# Street_Fighter_v1_3.net
KiCad netlist of a schematic drawn in EAGLE
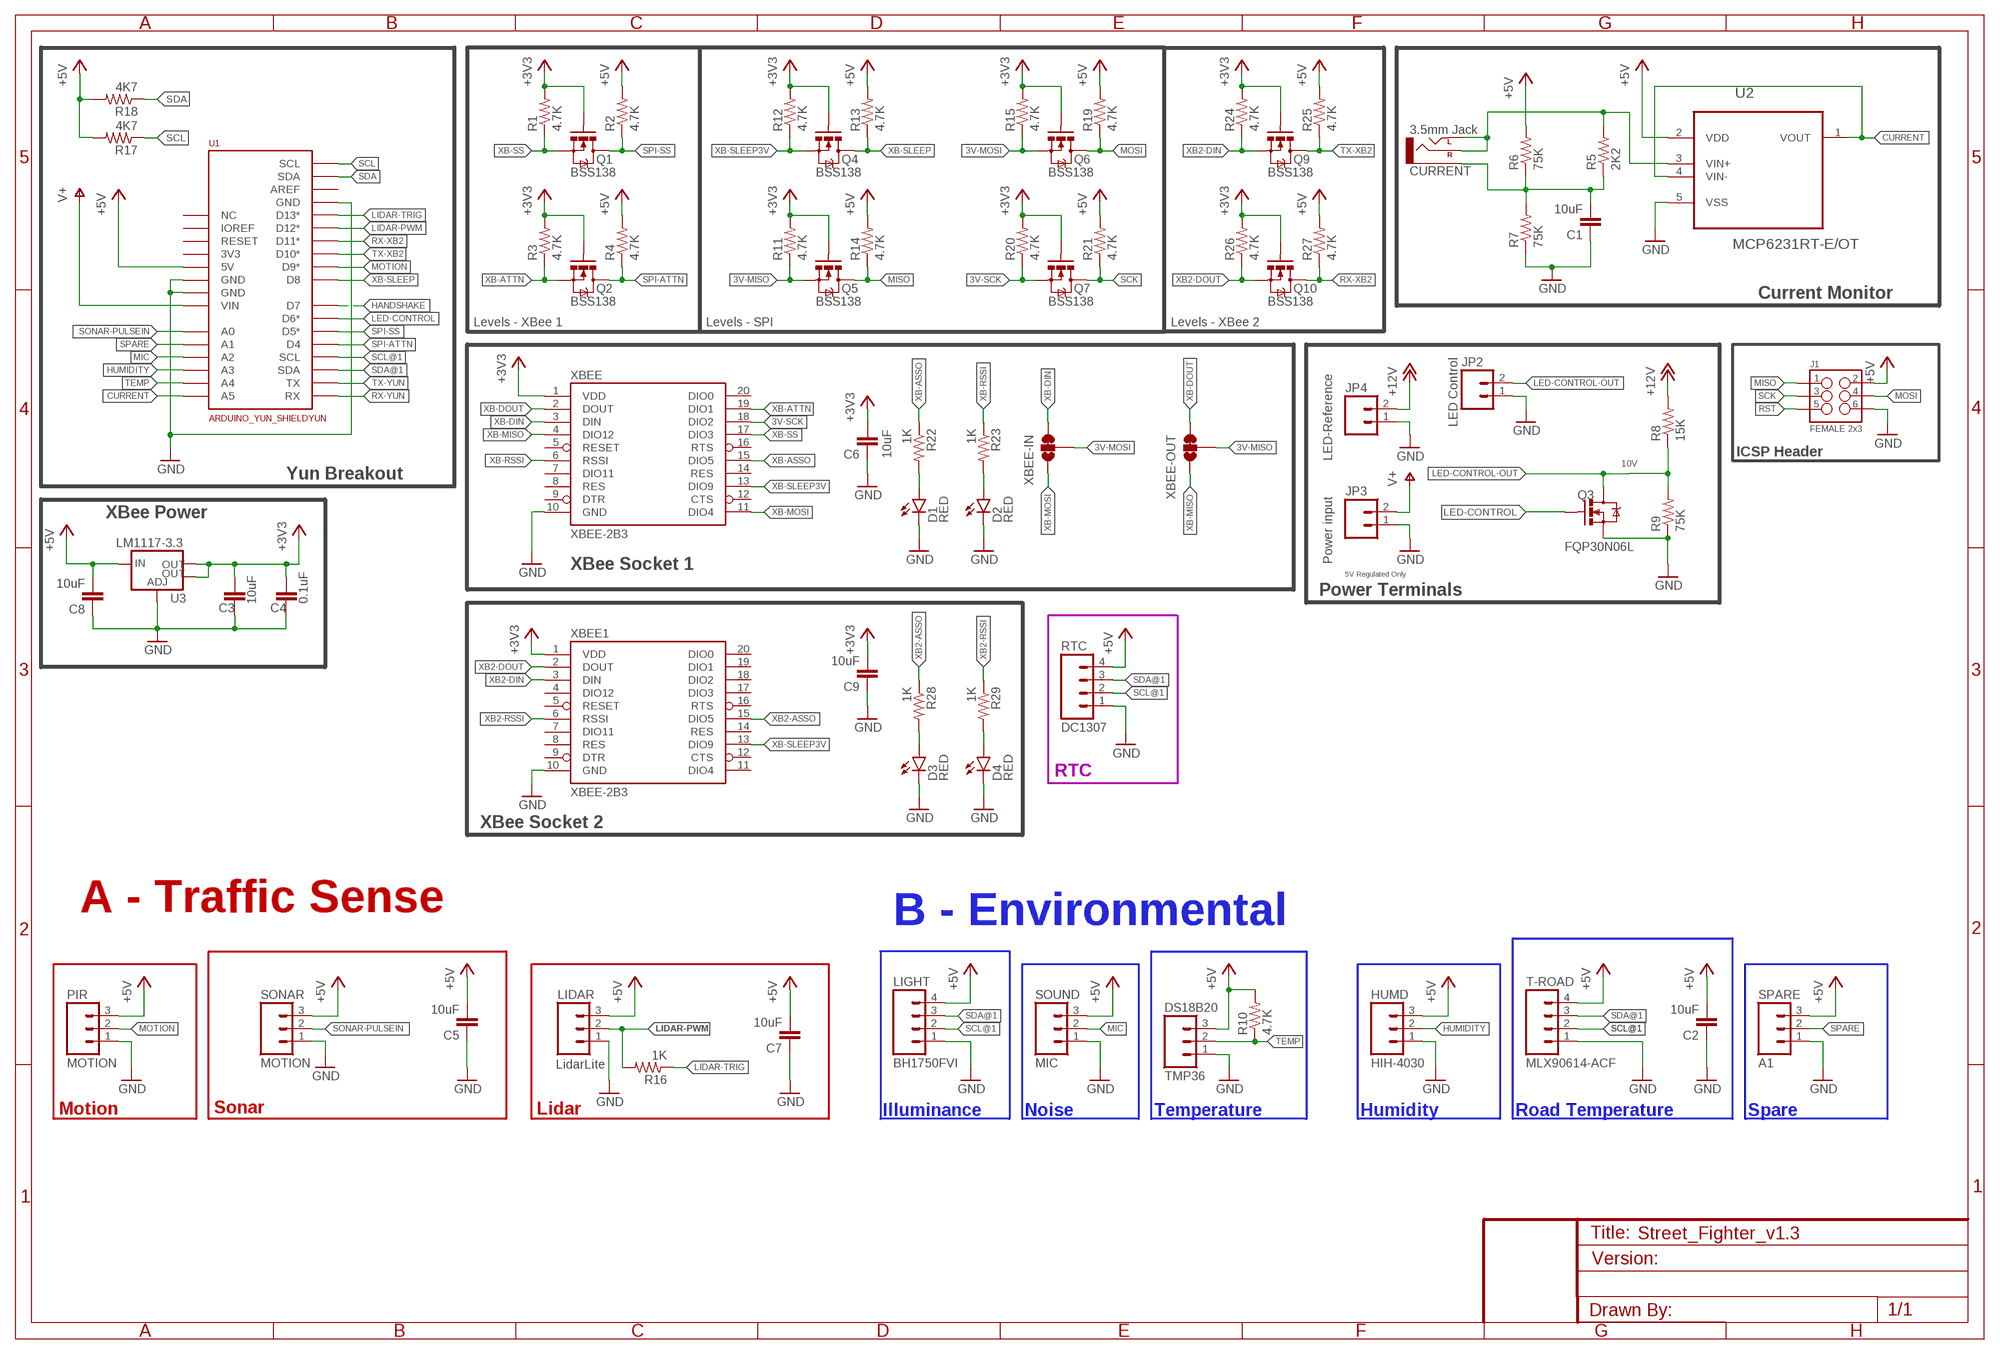
[diagram p0: schematic, sheet 1]

(export (version "E")
  (design (tool "Eeschema 10.0.6"))
  (components
    (comp (ref "C1")
      (value "10uF")
      (footprint "eagle-import:1206")
      (libsource (lib "eagle-import") (part "10UF-6.3V-20%(1206)"))
    )
    (comp (ref "C2")
      (value "10uF")
      (footprint "eagle-import:1206")
      (libsource (lib "eagle-import") (part "10UF-6.3V-20%(1206)"))
    )
    (comp (ref "C3")
      (value "10uF")
      (footprint "eagle-import:1206")
      (libsource (lib "eagle-import") (part "10UF-6.3V-20%(1206)"))
    )
    (comp (ref "C4")
      (value "0.1uF")
      (footprint "eagle-import:1206")
      (libsource (lib "eagle-import") (part "10UF-6.3V-20%(1206)"))
    )
    (comp (ref "C5")
      (value "10uF")
      (footprint "eagle-import:1206")
      (libsource (lib "eagle-import") (part "10UF-6.3V-20%(1206)"))
    )
    (comp (ref "C6")
      (value "10uF")
      (footprint "eagle-import:1206")
      (libsource (lib "eagle-import") (part "10UF-6.3V-20%(1206)"))
    )
    (comp (ref "C7")
      (value "10uF")
      (footprint "eagle-import:1206")
      (libsource (lib "eagle-import") (part "10UF-6.3V-20%(1206)"))
    )
    (comp (ref "C8")
      (value "10uF")
      (footprint "eagle-import:1206")
      (libsource (lib "eagle-import") (part "10UF-6.3V-20%(1206)"))
    )
    (comp (ref "C9")
      (value "10uF")
      (footprint "eagle-import:1206")
      (libsource (lib "eagle-import") (part "10UF-6.3V-20%(1206)"))
    )
    (comp (ref "CURRENT")
      (value "3.5mm Jack")
      (footprint "eagle-import:AUDIO-JACK")
      (libsource (lib "eagle-import") (part "AUDIO-JACKPTH"))
    )
    (comp (ref "D1")
      (value "RED")
      (footprint "eagle-import:LED-1206")
      (libsource (lib "eagle-import") (part "LED-RED1206"))
    )
    (comp (ref "D2")
      (value "RED")
      (footprint "eagle-import:LED-1206")
      (libsource (lib "eagle-import") (part "LED-RED1206"))
    )
    (comp (ref "D3")
      (value "RED")
      (footprint "eagle-import:LED-1206")
      (libsource (lib "eagle-import") (part "LED-RED1206"))
    )
    (comp (ref "D4")
      (value "RED")
      (footprint "eagle-import:LED-1206")
      (libsource (lib "eagle-import") (part "LED-RED1206"))
    )
    (comp (ref "DS18B20")
      (value "TMP36")
      (footprint "eagle-import:1X03")
      (libsource (lib "eagle-import") (part "M03PTH"))
    )
    (comp (ref "HUMD")
      (value "HIH-4030")
      (footprint "eagle-import:1X03")
      (libsource (lib "eagle-import") (part "M03PTH"))
    )
    (comp (ref "J1")
      (value "FEMALE 2x3")
      (footprint "eagle-import:2X3")
      (libsource (lib "eagle-import") (part "M03X2FEMALE"))
    )
    (comp (ref "JP2")
      (value "LED Control")
      (footprint "eagle-import:1X02_LONGPADS")
      (libsource (lib "eagle-import") (part "M02PTH3"))
    )
    (comp (ref "JP3")
      (value "Power input")
      (footprint "eagle-import:1X02_LONGPADS")
      (libsource (lib "eagle-import") (part "M02PTH3"))
    )
    (comp (ref "JP4")
      (value "LED-Reference")
      (footprint "eagle-import:1X02_LONGPADS")
      (libsource (lib "eagle-import") (part "M02PTH3"))
    )
    (comp (ref "LIDAR")
      (value "LidarLite")
      (footprint "eagle-import:1X03")
      (libsource (lib "eagle-import") (part "M03PTH"))
    )
    (comp (ref "LIGHT")
      (value "BH1750FVI")
      (footprint "eagle-import:1X04")
      (libsource (lib "eagle-import") (part "M04PTH"))
    )
    (comp (ref "PIR")
      (value "MOTION")
      (footprint "eagle-import:1X03")
      (libsource (lib "eagle-import") (part "M03PTH"))
    )
    (comp (ref "Q1")
      (value "BSS138")
      (footprint "eagle-import:SOT23")
      (libsource (lib "eagle-import") (part "MOSFET-NCHANNELBSS123LT1G"))
    )
    (comp (ref "Q2")
      (value "BSS138")
      (footprint "eagle-import:SOT23")
      (libsource (lib "eagle-import") (part "MOSFET-NCHANNELBSS123LT1G"))
    )
    (comp (ref "Q3")
      (value "FQP30N06L")
      (footprint "eagle-import:TO220V")
      (libsource (lib "eagle-import") (part "MOSFET-NCHANNELFQP30N06L"))
    )
    (comp (ref "Q4")
      (value "BSS138")
      (footprint "eagle-import:SOT23")
      (libsource (lib "eagle-import") (part "MOSFET-NCHANNELBSS123LT1G"))
    )
    (comp (ref "Q5")
      (value "BSS138")
      (footprint "eagle-import:SOT23")
      (libsource (lib "eagle-import") (part "MOSFET-NCHANNELBSS123LT1G"))
    )
    (comp (ref "Q6")
      (value "BSS138")
      (footprint "eagle-import:SOT23")
      (libsource (lib "eagle-import") (part "MOSFET-NCHANNELBSS123LT1G"))
    )
    (comp (ref "Q7")
      (value "BSS138")
      (footprint "eagle-import:SOT23")
      (libsource (lib "eagle-import") (part "MOSFET-NCHANNELBSS123LT1G"))
    )
    (comp (ref "Q9")
      (value "BSS138")
      (footprint "eagle-import:SOT23")
      (libsource (lib "eagle-import") (part "MOSFET-NCHANNELBSS123LT1G"))
    )
    (comp (ref "Q10")
      (value "BSS138")
      (footprint "eagle-import:SOT23")
      (libsource (lib "eagle-import") (part "MOSFET-NCHANNELBSS123LT1G"))
    )
    (comp (ref "R1")
      (value "4.7K")
      (footprint "eagle-import:1206")
      (libsource (lib "eagle-import") (part "RESISTOR1206"))
    )
    (comp (ref "R2")
      (value "4.7K")
      (footprint "eagle-import:1206")
      (libsource (lib "eagle-import") (part "RESISTOR1206"))
    )
    (comp (ref "R3")
      (value "4.7K")
      (footprint "eagle-import:1206")
      (libsource (lib "eagle-import") (part "RESISTOR1206"))
    )
    (comp (ref "R4")
      (value "4.7K")
      (footprint "eagle-import:1206")
      (libsource (lib "eagle-import") (part "RESISTOR1206"))
    )
    (comp (ref "R5")
      (value "2K2")
      (footprint "eagle-import:1206")
      (libsource (lib "eagle-import") (part "RESISTOR1206"))
    )
    (comp (ref "R6")
      (value "75K")
      (footprint "eagle-import:1206")
      (libsource (lib "eagle-import") (part "RESISTOR1206"))
    )
    (comp (ref "R7")
      (value "75K")
      (footprint "eagle-import:1206")
      (libsource (lib "eagle-import") (part "RESISTOR1206"))
    )
    (comp (ref "R8")
      (value "15K")
      (footprint "eagle-import:1206")
      (libsource (lib "eagle-import") (part "RESISTOR1206"))
    )
    (comp (ref "R9")
      (value "75K")
      (footprint "eagle-import:1206")
      (libsource (lib "eagle-import") (part "RESISTOR1206"))
    )
    (comp (ref "R10")
      (value "4.7K")
      (footprint "eagle-import:1206")
      (libsource (lib "eagle-import") (part "RESISTOR1206"))
    )
    (comp (ref "R11")
      (value "4.7K")
      (footprint "eagle-import:1206")
      (libsource (lib "eagle-import") (part "RESISTOR1206"))
    )
    (comp (ref "R12")
      (value "4.7K")
      (footprint "eagle-import:1206")
      (libsource (lib "eagle-import") (part "RESISTOR1206"))
    )
    (comp (ref "R13")
      (value "4.7K")
      (footprint "eagle-import:1206")
      (libsource (lib "eagle-import") (part "RESISTOR1206"))
    )
    (comp (ref "R14")
      (value "4.7K")
      (footprint "eagle-import:1206")
      (libsource (lib "eagle-import") (part "RESISTOR1206"))
    )
    (comp (ref "R15")
      (value "4.7K")
      (footprint "eagle-import:1206")
      (libsource (lib "eagle-import") (part "RESISTOR1206"))
    )
    (comp (ref "R16")
      (value "1K")
      (footprint "eagle-import:1206")
      (libsource (lib "eagle-import") (part "RESISTOR1206"))
    )
    (comp (ref "R17")
      (value "4K7")
      (footprint "eagle-import:1206")
      (libsource (lib "eagle-import") (part "RESISTOR1206"))
    )
    (comp (ref "R18")
      (value "4K7")
      (footprint "eagle-import:1206")
      (libsource (lib "eagle-import") (part "RESISTOR1206"))
    )
    (comp (ref "R19")
      (value "4.7K")
      (footprint "eagle-import:1206")
      (libsource (lib "eagle-import") (part "RESISTOR1206"))
    )
    (comp (ref "R20")
      (value "4.7K")
      (footprint "eagle-import:1206")
      (libsource (lib "eagle-import") (part "RESISTOR1206"))
    )
    (comp (ref "R21")
      (value "4.7K")
      (footprint "eagle-import:1206")
      (libsource (lib "eagle-import") (part "RESISTOR1206"))
    )
    (comp (ref "R22")
      (value "1K")
      (footprint "eagle-import:1206")
      (libsource (lib "eagle-import") (part "RESISTOR1206"))
    )
    (comp (ref "R23")
      (value "1K")
      (footprint "eagle-import:1206")
      (libsource (lib "eagle-import") (part "RESISTOR1206"))
    )
    (comp (ref "R24")
      (value "4.7K")
      (footprint "eagle-import:1206")
      (libsource (lib "eagle-import") (part "RESISTOR1206"))
    )
    (comp (ref "R25")
      (value "4.7K")
      (footprint "eagle-import:1206")
      (libsource (lib "eagle-import") (part "RESISTOR1206"))
    )
    (comp (ref "R26")
      (value "4.7K")
      (footprint "eagle-import:1206")
      (libsource (lib "eagle-import") (part "RESISTOR1206"))
    )
    (comp (ref "R27")
      (value "4.7K")
      (footprint "eagle-import:1206")
      (libsource (lib "eagle-import") (part "RESISTOR1206"))
    )
    (comp (ref "R28")
      (value "1K")
      (footprint "eagle-import:1206")
      (libsource (lib "eagle-import") (part "RESISTOR1206"))
    )
    (comp (ref "R29")
      (value "1K")
      (footprint "eagle-import:1206")
      (libsource (lib "eagle-import") (part "RESISTOR1206"))
    )
    (comp (ref "RTC")
      (value "DC1307")
      (footprint "eagle-import:1X04")
      (libsource (lib "eagle-import") (part "M04PTH"))
    )
    (comp (ref "SONAR")
      (value "MOTION")
      (footprint "eagle-import:1X03")
      (libsource (lib "eagle-import") (part "M03PTH"))
    )
    (comp (ref "SOUND")
      (value "MIC")
      (footprint "eagle-import:1X03")
      (libsource (lib "eagle-import") (part "M03PTH"))
    )
    (comp (ref "SPARE")
      (value "A1")
      (footprint "eagle-import:1X03")
      (libsource (lib "eagle-import") (part "M03PTH"))
    )
    (comp (ref "T-ROAD")
      (value "MLX90614-ACF")
      (footprint "eagle-import:1X04")
      (libsource (lib "eagle-import") (part "M04PTH"))
    )
    (comp (ref "U1")
      (value "ARDUINO_YUN_SHIELDYUN")
      (footprint "eagle-import:DUEMILANOVE_VIAS")
      (libsource (lib "eagle-import") (part "ARDUINO_YUN_SHIELDYUN"))
    )
    (comp (ref "U2")
      (value "MCP6231RT-E/OT")
      (footprint "eagle-import:SOT95P270X145-5N")
      (libsource (lib "eagle-import") (part "MCP6231RT-E/OT"))
    )
    (comp (ref "U3")
      (value "LM1117-3.3")
      (footprint "eagle-import:SOT223")
      (libsource (lib "eagle-import") (part "V_REG_LM1117SOT223"))
    )
    (comp (ref "XBEE")
      (value "XBEE-2B3")
      (footprint "eagle-import:XBEE-SMD")
      (libsource (lib "eagle-import") (part "XBEE-2B3"))
    )
    (comp (ref "XBEE-IN")
      (value "JUMPER-PAD-3-2OF3_NC_BY_TRACE_SMALL")
      (footprint "eagle-import:PAD-JUMPER-3-2OF3_NC_BY_TRACE_YES_SILK_FULL_BOX")
      (libsource (lib "eagle-import") (part "JUMPER-PAD-3-2OF3_NC_BY_TRACE_SMALL"))
    )
    (comp (ref "XBEE-OUT")
      (value "JUMPER-PAD-3-2OF3_NC_BY_TRACE_SMALL")
      (footprint "eagle-import:PAD-JUMPER-3-2OF3_NC_BY_TRACE_YES_SILK_FULL_BOX")
      (libsource (lib "eagle-import") (part "JUMPER-PAD-3-2OF3_NC_BY_TRACE_SMALL"))
    )
    (comp (ref "XBEE1")
      (value "XBEE-2B3")
      (footprint "eagle-import:XBEE-SMD")
      (libsource (lib "eagle-import") (part "XBEE-2B3"))
    )
  )
  (nets
    (net (code "1") (name "+3V3") (class "Default")
      (node (ref "C3") (pin "2") (pinfunction "2_2") (pintype "passive"))
      (node (ref "C4") (pin "2") (pinfunction "2_2") (pintype "passive"))
      (node (ref "C6") (pin "2") (pinfunction "2_2") (pintype "passive"))
      (node (ref "C9") (pin "2") (pinfunction "2_2") (pintype "passive"))
      (node (ref "Q1") (pin "1") (pinfunction "G_1") (pintype "passive"))
      (node (ref "Q10") (pin "1") (pinfunction "G_1") (pintype "passive"))
      (node (ref "Q2") (pin "1") (pinfunction "G_1") (pintype "passive"))
      (node (ref "Q4") (pin "1") (pinfunction "G_1") (pintype "passive"))
      (node (ref "Q5") (pin "1") (pinfunction "G_1") (pintype "passive"))
      (node (ref "Q6") (pin "1") (pinfunction "G_1") (pintype "passive"))
      (node (ref "Q7") (pin "1") (pinfunction "G_1") (pintype "passive"))
      (node (ref "Q9") (pin "1") (pinfunction "G_1") (pintype "passive"))
      (node (ref "R1") (pin "2") (pinfunction "2_2") (pintype "passive"))
      (node (ref "R11") (pin "2") (pinfunction "2_2") (pintype "passive"))
      (node (ref "R12") (pin "2") (pinfunction "2_2") (pintype "passive"))
      (node (ref "R15") (pin "2") (pinfunction "2_2") (pintype "passive"))
      (node (ref "R20") (pin "2") (pinfunction "2_2") (pintype "passive"))
      (node (ref "R24") (pin "2") (pinfunction "2_2") (pintype "passive"))
      (node (ref "R26") (pin "2") (pinfunction "2_2") (pintype "passive"))
      (node (ref "R3") (pin "2") (pinfunction "2_2") (pintype "passive"))
      (node (ref "U3") (pin "2") (pinfunction "OUT_2") (pintype "output"))
      (node (ref "U3") (pin "4") (pinfunction "OUT_4") (pintype "output"))
      (node (ref "XBEE") (pin "1") (pinfunction "VDD_1") (pintype "power_in"))
      (node (ref "XBEE1") (pin "1") (pinfunction "VDD_1") (pintype "power_in"))
    )
    (net (code "2") (name "+5V") (class "Default")
      (node (ref "C2") (pin "2") (pinfunction "2_2") (pintype "passive"))
      (node (ref "C5") (pin "2") (pinfunction "2_2") (pintype "passive"))
      (node (ref "C7") (pin "2") (pinfunction "2_2") (pintype "passive"))
      (node (ref "C8") (pin "2") (pinfunction "2_2") (pintype "passive"))
      (node (ref "DS18B20") (pin "3") (pinfunction "3_3") (pintype "passive"))
      (node (ref "HUMD") (pin "3") (pinfunction "3_3") (pintype "passive"))
      (node (ref "J1") (pin "2") (pinfunction "2_2") (pintype "bidirectional"))
      (node (ref "LIDAR") (pin "3") (pinfunction "3_3") (pintype "passive"))
      (node (ref "LIGHT") (pin "4") (pinfunction "4_4") (pintype "passive"))
      (node (ref "PIR") (pin "3") (pinfunction "3_3") (pintype "passive"))
      (node (ref "R10") (pin "2") (pinfunction "2_2") (pintype "passive"))
      (node (ref "R13") (pin "2") (pinfunction "2_2") (pintype "passive"))
      (node (ref "R14") (pin "2") (pinfunction "2_2") (pintype "passive"))
      (node (ref "R17") (pin "2") (pinfunction "2_2") (pintype "passive"))
      (node (ref "R18") (pin "2") (pinfunction "2_2") (pintype "passive"))
      (node (ref "R19") (pin "2") (pinfunction "2_2") (pintype "passive"))
      (node (ref "R2") (pin "2") (pinfunction "2_2") (pintype "passive"))
      (node (ref "R21") (pin "2") (pinfunction "2_2") (pintype "passive"))
      (node (ref "R25") (pin "2") (pinfunction "2_2") (pintype "passive"))
      (node (ref "R27") (pin "2") (pinfunction "2_2") (pintype "passive"))
      (node (ref "R4") (pin "2") (pinfunction "2_2") (pintype "passive"))
      (node (ref "R6") (pin "2") (pinfunction "2_2") (pintype "passive"))
      (node (ref "RTC") (pin "4") (pinfunction "4_4") (pintype "passive"))
      (node (ref "SONAR") (pin "3") (pinfunction "3_3") (pintype "passive"))
      (node (ref "SOUND") (pin "3") (pinfunction "3_3") (pintype "passive"))
      (node (ref "SPARE") (pin "3") (pinfunction "3_3") (pintype "passive"))
      (node (ref "T-ROAD") (pin "4") (pinfunction "4_4") (pintype "passive"))
      (node (ref "U1") (pin "5V") (pinfunction "5V_5V") (pintype "power_in"))
      (node (ref "U2") (pin "2") (pinfunction "VDD_2") (pintype "power_in"))
      (node (ref "U3") (pin "3") (pinfunction "IN_3") (pintype "input"))
    )
    (net (code "3") (name "+12V") (class "Default")
      (node (ref "JP4") (pin "2") (pinfunction "2_2") (pintype "passive"))
      (node (ref "R8") (pin "2") (pinfunction "2_2") (pintype "passive"))
    )
    (net (code "4") (name "/3V3") (class "Default")
      (node (ref "U1") (pin "3V3") (pinfunction "3V3_3V3") (pintype "power_in"))
    )
    (net (code "5") (name "3V-MISO") (class "Default")
      (node (ref "Q5") (pin "2") (pinfunction "S_2") (pintype "passive"))
      (node (ref "R11") (pin "1") (pinfunction "1_1") (pintype "passive"))
      (node (ref "XBEE-OUT") (pin "2") (pinfunction "2_2") (pintype "passive"))
    )
    (net (code "6") (name "3V-MOSI") (class "Default")
      (node (ref "Q6") (pin "2") (pinfunction "S_2") (pintype "passive"))
      (node (ref "R15") (pin "1") (pinfunction "1_1") (pintype "passive"))
      (node (ref "XBEE-IN") (pin "2") (pinfunction "2_2") (pintype "passive"))
    )
    (net (code "7") (name "3V-SCK") (class "Default")
      (node (ref "Q7") (pin "2") (pinfunction "S_2") (pintype "passive"))
      (node (ref "R20") (pin "1") (pinfunction "1_1") (pintype "passive"))
      (node (ref "XBEE") (pin "18") (pinfunction "DIO2_18") (pintype "bidirectional"))
    )
    (net (code "8") (name "CURRENT") (class "Default")
      (node (ref "U1") (pin "A5") (pinfunction "A5_A5") (pintype "bidirectional"))
      (node (ref "U2") (pin "1") (pinfunction "VOUT_1") (pintype "output"))
      (node (ref "U2") (pin "4") (pinfunction "VIN-_4") (pintype "input"))
    )
    (net (code "9") (name "GND") (class "Default")
      (node (ref "C1") (pin "1") (pinfunction "1_1") (pintype "passive"))
      (node (ref "C2") (pin "1") (pinfunction "1_1") (pintype "passive"))
      (node (ref "C3") (pin "1") (pinfunction "1_1") (pintype "passive"))
      (node (ref "C4") (pin "1") (pinfunction "1_1") (pintype "passive"))
      (node (ref "C5") (pin "1") (pinfunction "1_1") (pintype "passive"))
      (node (ref "C6") (pin "1") (pinfunction "1_1") (pintype "passive"))
      (node (ref "C7") (pin "1") (pinfunction "1_1") (pintype "passive"))
      (node (ref "C8") (pin "1") (pinfunction "1_1") (pintype "passive"))
      (node (ref "C9") (pin "1") (pinfunction "1_1") (pintype "passive"))
      (node (ref "D1") (pin "C") (pinfunction "C_C") (pintype "passive"))
      (node (ref "D2") (pin "C") (pinfunction "C_C") (pintype "passive"))
      (node (ref "D3") (pin "C") (pinfunction "C_C") (pintype "passive"))
      (node (ref "D4") (pin "C") (pinfunction "C_C") (pintype "passive"))
      (node (ref "DS18B20") (pin "1") (pinfunction "1_1") (pintype "passive"))
      (node (ref "HUMD") (pin "1") (pinfunction "1_1") (pintype "passive"))
      (node (ref "J1") (pin "6") (pinfunction "6_6") (pintype "bidirectional"))
      (node (ref "JP2") (pin "1") (pinfunction "1_1") (pintype "passive"))
      (node (ref "JP3") (pin "1") (pinfunction "1_1") (pintype "passive"))
      (node (ref "JP4") (pin "1") (pinfunction "1_1") (pintype "passive"))
      (node (ref "LIDAR") (pin "1") (pinfunction "1_1") (pintype "passive"))
      (node (ref "LIGHT") (pin "1") (pinfunction "1_1") (pintype "passive"))
      (node (ref "PIR") (pin "1") (pinfunction "1_1") (pintype "passive"))
      (node (ref "Q3") (pin "3") (pinfunction "S_3") (pintype "passive"))
      (node (ref "R7") (pin "1") (pinfunction "1_1") (pintype "passive"))
      (node (ref "R9") (pin "1") (pinfunction "1_1") (pintype "passive"))
      (node (ref "RTC") (pin "1") (pinfunction "1_1") (pintype "passive"))
      (node (ref "SONAR") (pin "1") (pinfunction "1_1") (pintype "passive"))
      (node (ref "SOUND") (pin "1") (pinfunction "1_1") (pintype "passive"))
      (node (ref "SPARE") (pin "1") (pinfunction "1_1") (pintype "passive"))
      (node (ref "T-ROAD") (pin "1") (pinfunction "1_1") (pintype "passive"))
      (node (ref "U1") (pin "GND") (pinfunction "GND_GND") (pintype "power_in"))
      (node (ref "U1") (pin "GND@0") (pinfunction "GND_GND@0") (pintype "power_in"))
      (node (ref "U1") (pin "GND@1") (pinfunction "GND_GND@1") (pintype "power_in"))
      (node (ref "U2") (pin "5") (pinfunction "VSS_5") (pintype "passive"))
      (node (ref "U3") (pin "1") (pinfunction "ADJ_1") (pintype "input"))
      (node (ref "XBEE") (pin "10") (pinfunction "GND_10") (pintype "power_in"))
      (node (ref "XBEE1") (pin "10") (pinfunction "GND_10") (pintype "power_in"))
    )
    (net (code "10") (name "HANDSHAKE") (class "Default")
      (node (ref "U1") (pin "7") (pinfunction "D7_7") (pintype "bidirectional"))
    )
    (net (code "11") (name "HUMIDITY") (class "Default")
      (node (ref "HUMD") (pin "2") (pinfunction "2_2") (pintype "passive"))
      (node (ref "U1") (pin "A3") (pinfunction "A3_A3") (pintype "bidirectional"))
    )
    (net (code "12") (name "LED-CONTROL") (class "Default")
      (node (ref "Q3") (pin "1") (pinfunction "G_1") (pintype "passive"))
      (node (ref "U1") (pin "6") (pinfunction "D6*_6") (pintype "bidirectional"))
    )
    (net (code "13") (name "LED-CONTROL-OUT") (class "Default")
      (node (ref "JP2") (pin "2") (pinfunction "2_2") (pintype "passive"))
      (node (ref "Q3") (pin "2") (pinfunction "D_2") (pintype "passive"))
      (node (ref "R8") (pin "1") (pinfunction "1_1") (pintype "passive"))
      (node (ref "R9") (pin "2") (pinfunction "2_2") (pintype "passive"))
    )
    (net (code "14") (name "LIDAR-PWM") (class "Default")
      (node (ref "LIDAR") (pin "2") (pinfunction "2_2") (pintype "passive"))
      (node (ref "R16") (pin "2") (pinfunction "2_2") (pintype "passive"))
      (node (ref "U1") (pin "12") (pinfunction "D12*_12") (pintype "bidirectional"))
    )
    (net (code "15") (name "LIDAR-TRIG") (class "Default")
      (node (ref "R16") (pin "1") (pinfunction "1_1") (pintype "passive"))
      (node (ref "U1") (pin "13") (pinfunction "D13*_13") (pintype "bidirectional"))
    )
    (net (code "16") (name "MIC") (class "Default")
      (node (ref "SOUND") (pin "2") (pinfunction "2_2") (pintype "passive"))
      (node (ref "U1") (pin "A2") (pinfunction "A2_A2") (pintype "bidirectional"))
    )
    (net (code "17") (name "MISO") (class "Default")
      (node (ref "J1") (pin "1") (pinfunction "1_1") (pintype "bidirectional"))
      (node (ref "Q5") (pin "3") (pinfunction "D_3") (pintype "passive"))
      (node (ref "R14") (pin "1") (pinfunction "1_1") (pintype "passive"))
    )
    (net (code "18") (name "MOSI") (class "Default")
      (node (ref "J1") (pin "4") (pinfunction "4_4") (pintype "bidirectional"))
      (node (ref "Q6") (pin "3") (pinfunction "D_3") (pintype "passive"))
      (node (ref "R19") (pin "1") (pinfunction "1_1") (pintype "passive"))
    )
    (net (code "19") (name "MOTION") (class "Default")
      (node (ref "PIR") (pin "2") (pinfunction "2_2") (pintype "passive"))
      (node (ref "U1") (pin "9") (pinfunction "D9*_9") (pintype "bidirectional"))
    )
    (net (code "20") (name "Net-(C1-Pad2)") (class "Default")
      (node (ref "C1") (pin "2") (pinfunction "2_2") (pintype "passive"))
      (node (ref "CURRENT") (pin "SLEEVE") (pinfunction "SLEEVE_SLEEVE") (pintype "bidirectional"))
      (node (ref "R5") (pin "1") (pinfunction "1_1") (pintype "passive"))
      (node (ref "R6") (pin "1") (pinfunction "1_1") (pintype "passive"))
      (node (ref "R7") (pin "2") (pinfunction "2_2") (pintype "passive"))
    )
    (net (code "21") (name "Net-(CURRENT-LEFT)") (class "Default")
      (node (ref "CURRENT") (pin "RING") (pinfunction "RIGHT_RING") (pintype "bidirectional"))
      (node (ref "CURRENT") (pin "TIP") (pinfunction "LEFT_TIP") (pintype "bidirectional"))
      (node (ref "R5") (pin "2") (pinfunction "2_2") (pintype "passive"))
      (node (ref "U2") (pin "3") (pinfunction "VIN+_3") (pintype "input"))
    )
    (net (code "22") (name "Net-(D1-PadA)") (class "Default")
      (node (ref "D1") (pin "A") (pinfunction "A_A") (pintype "passive"))
      (node (ref "R22") (pin "2") (pinfunction "2_2") (pintype "passive"))
    )
    (net (code "23") (name "Net-(D2-PadA)") (class "Default")
      (node (ref "D2") (pin "A") (pinfunction "A_A") (pintype "passive"))
      (node (ref "R23") (pin "2") (pinfunction "2_2") (pintype "passive"))
    )
    (net (code "24") (name "Net-(D3-PadA)") (class "Default")
      (node (ref "D3") (pin "A") (pinfunction "A_A") (pintype "passive"))
      (node (ref "R28") (pin "2") (pinfunction "2_2") (pintype "passive"))
    )
    (net (code "25") (name "Net-(D4-PadA)") (class "Default")
      (node (ref "D4") (pin "A") (pinfunction "A_A") (pintype "passive"))
      (node (ref "R29") (pin "2") (pinfunction "2_2") (pintype "passive"))
    )
    (net (code "26") (name "RST") (class "Default")
      (node (ref "J1") (pin "5") (pinfunction "5_5") (pintype "bidirectional"))
    )
    (net (code "27") (name "RX-XB2") (class "Default")
      (node (ref "Q10") (pin "3") (pinfunction "D_3") (pintype "passive"))
      (node (ref "R27") (pin "1") (pinfunction "1_1") (pintype "passive"))
      (node (ref "U1") (pin "11") (pinfunction "D11*_11") (pintype "bidirectional"))
    )
    (net (code "28") (name "RX-YUN") (class "Default")
      (node (ref "U1") (pin "0") (pinfunction "RX_0") (pintype "bidirectional"))
    )
    (net (code "29") (name "SCK") (class "Default")
      (node (ref "J1") (pin "3") (pinfunction "3_3") (pintype "bidirectional"))
      (node (ref "Q7") (pin "3") (pinfunction "D_3") (pintype "passive"))
      (node (ref "R21") (pin "1") (pinfunction "1_1") (pintype "passive"))
    )
    (net (code "30") (name "SCL") (class "Default")
      (node (ref "R17") (pin "1") (pinfunction "1_1") (pintype "passive"))
      (node (ref "U1") (pin "3@1") (pinfunction "SCL_3@1") (pintype "bidirectional"))
    )
    (net (code "31") (name "SCL@1") (class "Default")
      (node (ref "LIGHT") (pin "2") (pinfunction "2_2") (pintype "passive"))
      (node (ref "RTC") (pin "2") (pinfunction "2_2") (pintype "passive"))
      (node (ref "T-ROAD") (pin "2") (pinfunction "2_2") (pintype "passive"))
      (node (ref "U1") (pin "3") (pinfunction "SCL_3") (pintype "bidirectional"))
    )
    (net (code "32") (name "SDA") (class "Default")
      (node (ref "R18") (pin "1") (pinfunction "1_1") (pintype "passive"))
      (node (ref "U1") (pin "2@1") (pinfunction "SDA_2@1") (pintype "bidirectional"))
    )
    (net (code "33") (name "SDA@1") (class "Default")
      (node (ref "LIGHT") (pin "3") (pinfunction "3_3") (pintype "passive"))
      (node (ref "RTC") (pin "3") (pinfunction "3_3") (pintype "passive"))
      (node (ref "T-ROAD") (pin "3") (pinfunction "3_3") (pintype "passive"))
      (node (ref "U1") (pin "2") (pinfunction "SDA_2") (pintype "bidirectional"))
    )
    (net (code "34") (name "SONAR-PULSEIN") (class "Default")
      (node (ref "SONAR") (pin "2") (pinfunction "2_2") (pintype "passive"))
      (node (ref "U1") (pin "A0") (pinfunction "A0_A0") (pintype "bidirectional"))
    )
    (net (code "35") (name "SPARE") (class "Default")
      (node (ref "SPARE") (pin "2") (pinfunction "2_2") (pintype "passive"))
      (node (ref "U1") (pin "A1") (pinfunction "A1_A1") (pintype "bidirectional"))
    )
    (net (code "36") (name "SPI-ATTN") (class "Default")
      (node (ref "Q2") (pin "3") (pinfunction "D_3") (pintype "passive"))
      (node (ref "R4") (pin "1") (pinfunction "1_1") (pintype "passive"))
      (node (ref "U1") (pin "D4") (pinfunction "D4_D4") (pintype "bidirectional"))
    )
    (net (code "37") (name "SPI-SS") (class "Default")
      (node (ref "Q1") (pin "3") (pinfunction "D_3") (pintype "passive"))
      (node (ref "R2") (pin "1") (pinfunction "1_1") (pintype "passive"))
      (node (ref "U1") (pin "5") (pinfunction "D5*_5") (pintype "bidirectional"))
    )
    (net (code "38") (name "TEMP") (class "Default")
      (node (ref "DS18B20") (pin "2") (pinfunction "2_2") (pintype "passive"))
      (node (ref "R10") (pin "1") (pinfunction "1_1") (pintype "passive"))
      (node (ref "U1") (pin "A4") (pinfunction "A4_A4") (pintype "bidirectional"))
    )
    (net (code "39") (name "TX-XB2") (class "Default")
      (node (ref "Q9") (pin "3") (pinfunction "D_3") (pintype "passive"))
      (node (ref "R25") (pin "1") (pinfunction "1_1") (pintype "passive"))
      (node (ref "U1") (pin "10") (pinfunction "D10*_10") (pintype "bidirectional"))
    )
    (net (code "40") (name "TX-YUN") (class "Default")
      (node (ref "U1") (pin "1") (pinfunction "TX_1") (pintype "bidirectional"))
    )
    (net (code "41") (name "V+") (class "Default")
      (node (ref "JP3") (pin "2") (pinfunction "2_2") (pintype "passive"))
      (node (ref "U1") (pin "VIN") (pinfunction "VIN_VIN") (pintype "power_in"))
    )
    (net (code "42") (name "XB-ASSO") (class "Default")
      (node (ref "R22") (pin "1") (pinfunction "1_1") (pintype "passive"))
      (node (ref "XBEE") (pin "15") (pinfunction "DIO5_15") (pintype "bidirectional"))
    )
    (net (code "43") (name "XB-ATTN") (class "Default")
      (node (ref "Q2") (pin "2") (pinfunction "S_2") (pintype "passive"))
      (node (ref "R3") (pin "1") (pinfunction "1_1") (pintype "passive"))
      (node (ref "XBEE") (pin "19") (pinfunction "DIO1_19") (pintype "bidirectional"))
    )
    (net (code "44") (name "XB-DIN") (class "Default")
      (node (ref "XBEE") (pin "3") (pinfunction "DIN_3") (pintype "input"))
      (node (ref "XBEE-IN") (pin "3") (pinfunction "3_3") (pintype "passive"))
    )
    (net (code "45") (name "XB-DOUT") (class "Default")
      (node (ref "XBEE") (pin "2") (pinfunction "DOUT_2") (pintype "output"))
      (node (ref "XBEE-OUT") (pin "3") (pinfunction "3_3") (pintype "passive"))
    )
    (net (code "46") (name "XB-MISO") (class "Default")
      (node (ref "XBEE") (pin "4") (pinfunction "DIO12_4") (pintype "bidirectional"))
      (node (ref "XBEE-OUT") (pin "1") (pinfunction "1_1") (pintype "passive"))
    )
    (net (code "47") (name "XB-MOSI") (class "Default")
      (node (ref "XBEE") (pin "11") (pinfunction "DIO4_11") (pintype "bidirectional"))
      (node (ref "XBEE-IN") (pin "1") (pinfunction "1_1") (pintype "passive"))
    )
    (net (code "48") (name "XB-RSSI") (class "Default")
      (node (ref "R23") (pin "1") (pinfunction "1_1") (pintype "passive"))
      (node (ref "XBEE") (pin "6") (pinfunction "RSSI_6") (pintype "bidirectional"))
    )
    (net (code "49") (name "XB-SLEEP") (class "Default")
      (node (ref "Q4") (pin "3") (pinfunction "D_3") (pintype "passive"))
      (node (ref "R13") (pin "1") (pinfunction "1_1") (pintype "passive"))
      (node (ref "U1") (pin "8") (pinfunction "D8_8") (pintype "bidirectional"))
    )
    (net (code "50") (name "XB-SLEEP3V") (class "Default")
      (node (ref "Q4") (pin "2") (pinfunction "S_2") (pintype "passive"))
      (node (ref "R12") (pin "1") (pinfunction "1_1") (pintype "passive"))
      (node (ref "XBEE") (pin "13") (pinfunction "DIO9_13") (pintype "bidirectional"))
      (node (ref "XBEE1") (pin "13") (pinfunction "DIO9_13") (pintype "bidirectional"))
    )
    (net (code "51") (name "XB-SS") (class "Default")
      (node (ref "Q1") (pin "2") (pinfunction "S_2") (pintype "passive"))
      (node (ref "R1") (pin "1") (pinfunction "1_1") (pintype "passive"))
      (node (ref "XBEE") (pin "17") (pinfunction "DIO3_17") (pintype "bidirectional"))
    )
    (net (code "52") (name "XB2-ASSO") (class "Default")
      (node (ref "R28") (pin "1") (pinfunction "1_1") (pintype "passive"))
      (node (ref "XBEE1") (pin "15") (pinfunction "DIO5_15") (pintype "bidirectional"))
    )
    (net (code "53") (name "XB2-DIN") (class "Default")
      (node (ref "Q9") (pin "2") (pinfunction "S_2") (pintype "passive"))
      (node (ref "R24") (pin "1") (pinfunction "1_1") (pintype "passive"))
      (node (ref "XBEE1") (pin "3") (pinfunction "DIN_3") (pintype "input"))
    )
    (net (code "54") (name "XB2-DOUT") (class "Default")
      (node (ref "Q10") (pin "2") (pinfunction "S_2") (pintype "passive"))
      (node (ref "R26") (pin "1") (pinfunction "1_1") (pintype "passive"))
      (node (ref "XBEE1") (pin "2") (pinfunction "DOUT_2") (pintype "output"))
    )
    (net (code "55") (name "XB2-RSSI") (class "Default")
      (node (ref "R29") (pin "1") (pinfunction "1_1") (pintype "passive"))
      (node (ref "XBEE1") (pin "6") (pinfunction "RSSI_6") (pintype "bidirectional"))
    )
    (net (code "56") (name "unconnected-(U1-PadAREF)") (class "Default")
      (node (ref "U1") (pin "AREF") (pinfunction "AREF_AREF") (pintype "bidirectional"))
    )
    (net (code "57") (name "unconnected-(U1-PadIOREF)") (class "Default")
      (node (ref "U1") (pin "IOREF") (pinfunction "IOREF_IOREF") (pintype "bidirectional"))
    )
    (net (code "58") (name "unconnected-(U1-PadNC)") (class "Default")
      (node (ref "U1") (pin "NC") (pinfunction "NC_NC") (pintype "no_connect"))
    )
    (net (code "59") (name "unconnected-(U1-PadRESET)") (class "Default")
      (node (ref "U1") (pin "RESET") (pinfunction "RESET_RESET") (pintype "bidirectional"))
    )
    (net (code "60") (name "unconnected-(XBEE-CTS-Pad12)") (class "Default")
      (node (ref "XBEE") (pin "12") (pinfunction "CTS_12") (pintype "output"))
    )
    (net (code "61") (name "unconnected-(XBEE-DIO0-Pad20)") (class "Default")
      (node (ref "XBEE") (pin "20") (pinfunction "DIO0_20") (pintype "bidirectional"))
    )
    (net (code "62") (name "unconnected-(XBEE-DIO11-Pad7)") (class "Default")
      (node (ref "XBEE") (pin "7") (pinfunction "DIO11_7") (pintype "bidirectional"))
    )
    (net (code "63") (name "unconnected-(XBEE-DTR-Pad9)") (class "Default")
      (node (ref "XBEE") (pin "9") (pinfunction "DTR_9") (pintype "bidirectional"))
    )
    (net (code "64") (name "unconnected-(XBEE-RES-Pad8)") (class "Default")
      (node (ref "XBEE") (pin "8") (pinfunction "RES_8") (pintype "bidirectional"))
    )
    (net (code "65") (name "unconnected-(XBEE-RES-Pad14)") (class "Default")
      (node (ref "XBEE") (pin "14") (pinfunction "RES_14") (pintype "bidirectional"))
    )
    (net (code "66") (name "unconnected-(XBEE-RESET-Pad5)") (class "Default")
      (node (ref "XBEE") (pin "5") (pinfunction "RESET_5") (pintype "input"))
    )
    (net (code "67") (name "unconnected-(XBEE-RTS-Pad16)") (class "Default")
      (node (ref "XBEE") (pin "16") (pinfunction "RTS_16") (pintype "input"))
    )
    (net (code "68") (name "unconnected-(XBEE1-CTS-Pad12)") (class "Default")
      (node (ref "XBEE1") (pin "12") (pinfunction "CTS_12") (pintype "output"))
    )
    (net (code "69") (name "unconnected-(XBEE1-DIO0-Pad20)") (class "Default")
      (node (ref "XBEE1") (pin "20") (pinfunction "DIO0_20") (pintype "bidirectional"))
    )
    (net (code "70") (name "unconnected-(XBEE1-DIO1-Pad19)") (class "Default")
      (node (ref "XBEE1") (pin "19") (pinfunction "DIO1_19") (pintype "bidirectional"))
    )
    (net (code "71") (name "unconnected-(XBEE1-DIO2-Pad18)") (class "Default")
      (node (ref "XBEE1") (pin "18") (pinfunction "DIO2_18") (pintype "bidirectional"))
    )
    (net (code "72") (name "unconnected-(XBEE1-DIO3-Pad17)") (class "Default")
      (node (ref "XBEE1") (pin "17") (pinfunction "DIO3_17") (pintype "bidirectional"))
    )
    (net (code "73") (name "unconnected-(XBEE1-DIO4-Pad11)") (class "Default")
      (node (ref "XBEE1") (pin "11") (pinfunction "DIO4_11") (pintype "bidirectional"))
    )
    (net (code "74") (name "unconnected-(XBEE1-DIO11-Pad7)") (class "Default")
      (node (ref "XBEE1") (pin "7") (pinfunction "DIO11_7") (pintype "bidirectional"))
    )
    (net (code "75") (name "unconnected-(XBEE1-DIO12-Pad4)") (class "Default")
      (node (ref "XBEE1") (pin "4") (pinfunction "DIO12_4") (pintype "bidirectional"))
    )
    (net (code "76") (name "unconnected-(XBEE1-DTR-Pad9)") (class "Default")
      (node (ref "XBEE1") (pin "9") (pinfunction "DTR_9") (pintype "bidirectional"))
    )
    (net (code "77") (name "unconnected-(XBEE1-RES-Pad8)") (class "Default")
      (node (ref "XBEE1") (pin "8") (pinfunction "RES_8") (pintype "bidirectional"))
    )
    (net (code "78") (name "unconnected-(XBEE1-RES-Pad14)") (class "Default")
      (node (ref "XBEE1") (pin "14") (pinfunction "RES_14") (pintype "bidirectional"))
    )
    (net (code "79") (name "unconnected-(XBEE1-RESET-Pad5)") (class "Default")
      (node (ref "XBEE1") (pin "5") (pinfunction "RESET_5") (pintype "input"))
    )
    (net (code "80") (name "unconnected-(XBEE1-RTS-Pad16)") (class "Default")
      (node (ref "XBEE1") (pin "16") (pinfunction "RTS_16") (pintype "input"))
    )
  )
)
